# 1-Schematic_EE463_Project.net
KiCad netlist of a schematic drawn in EasyEDA
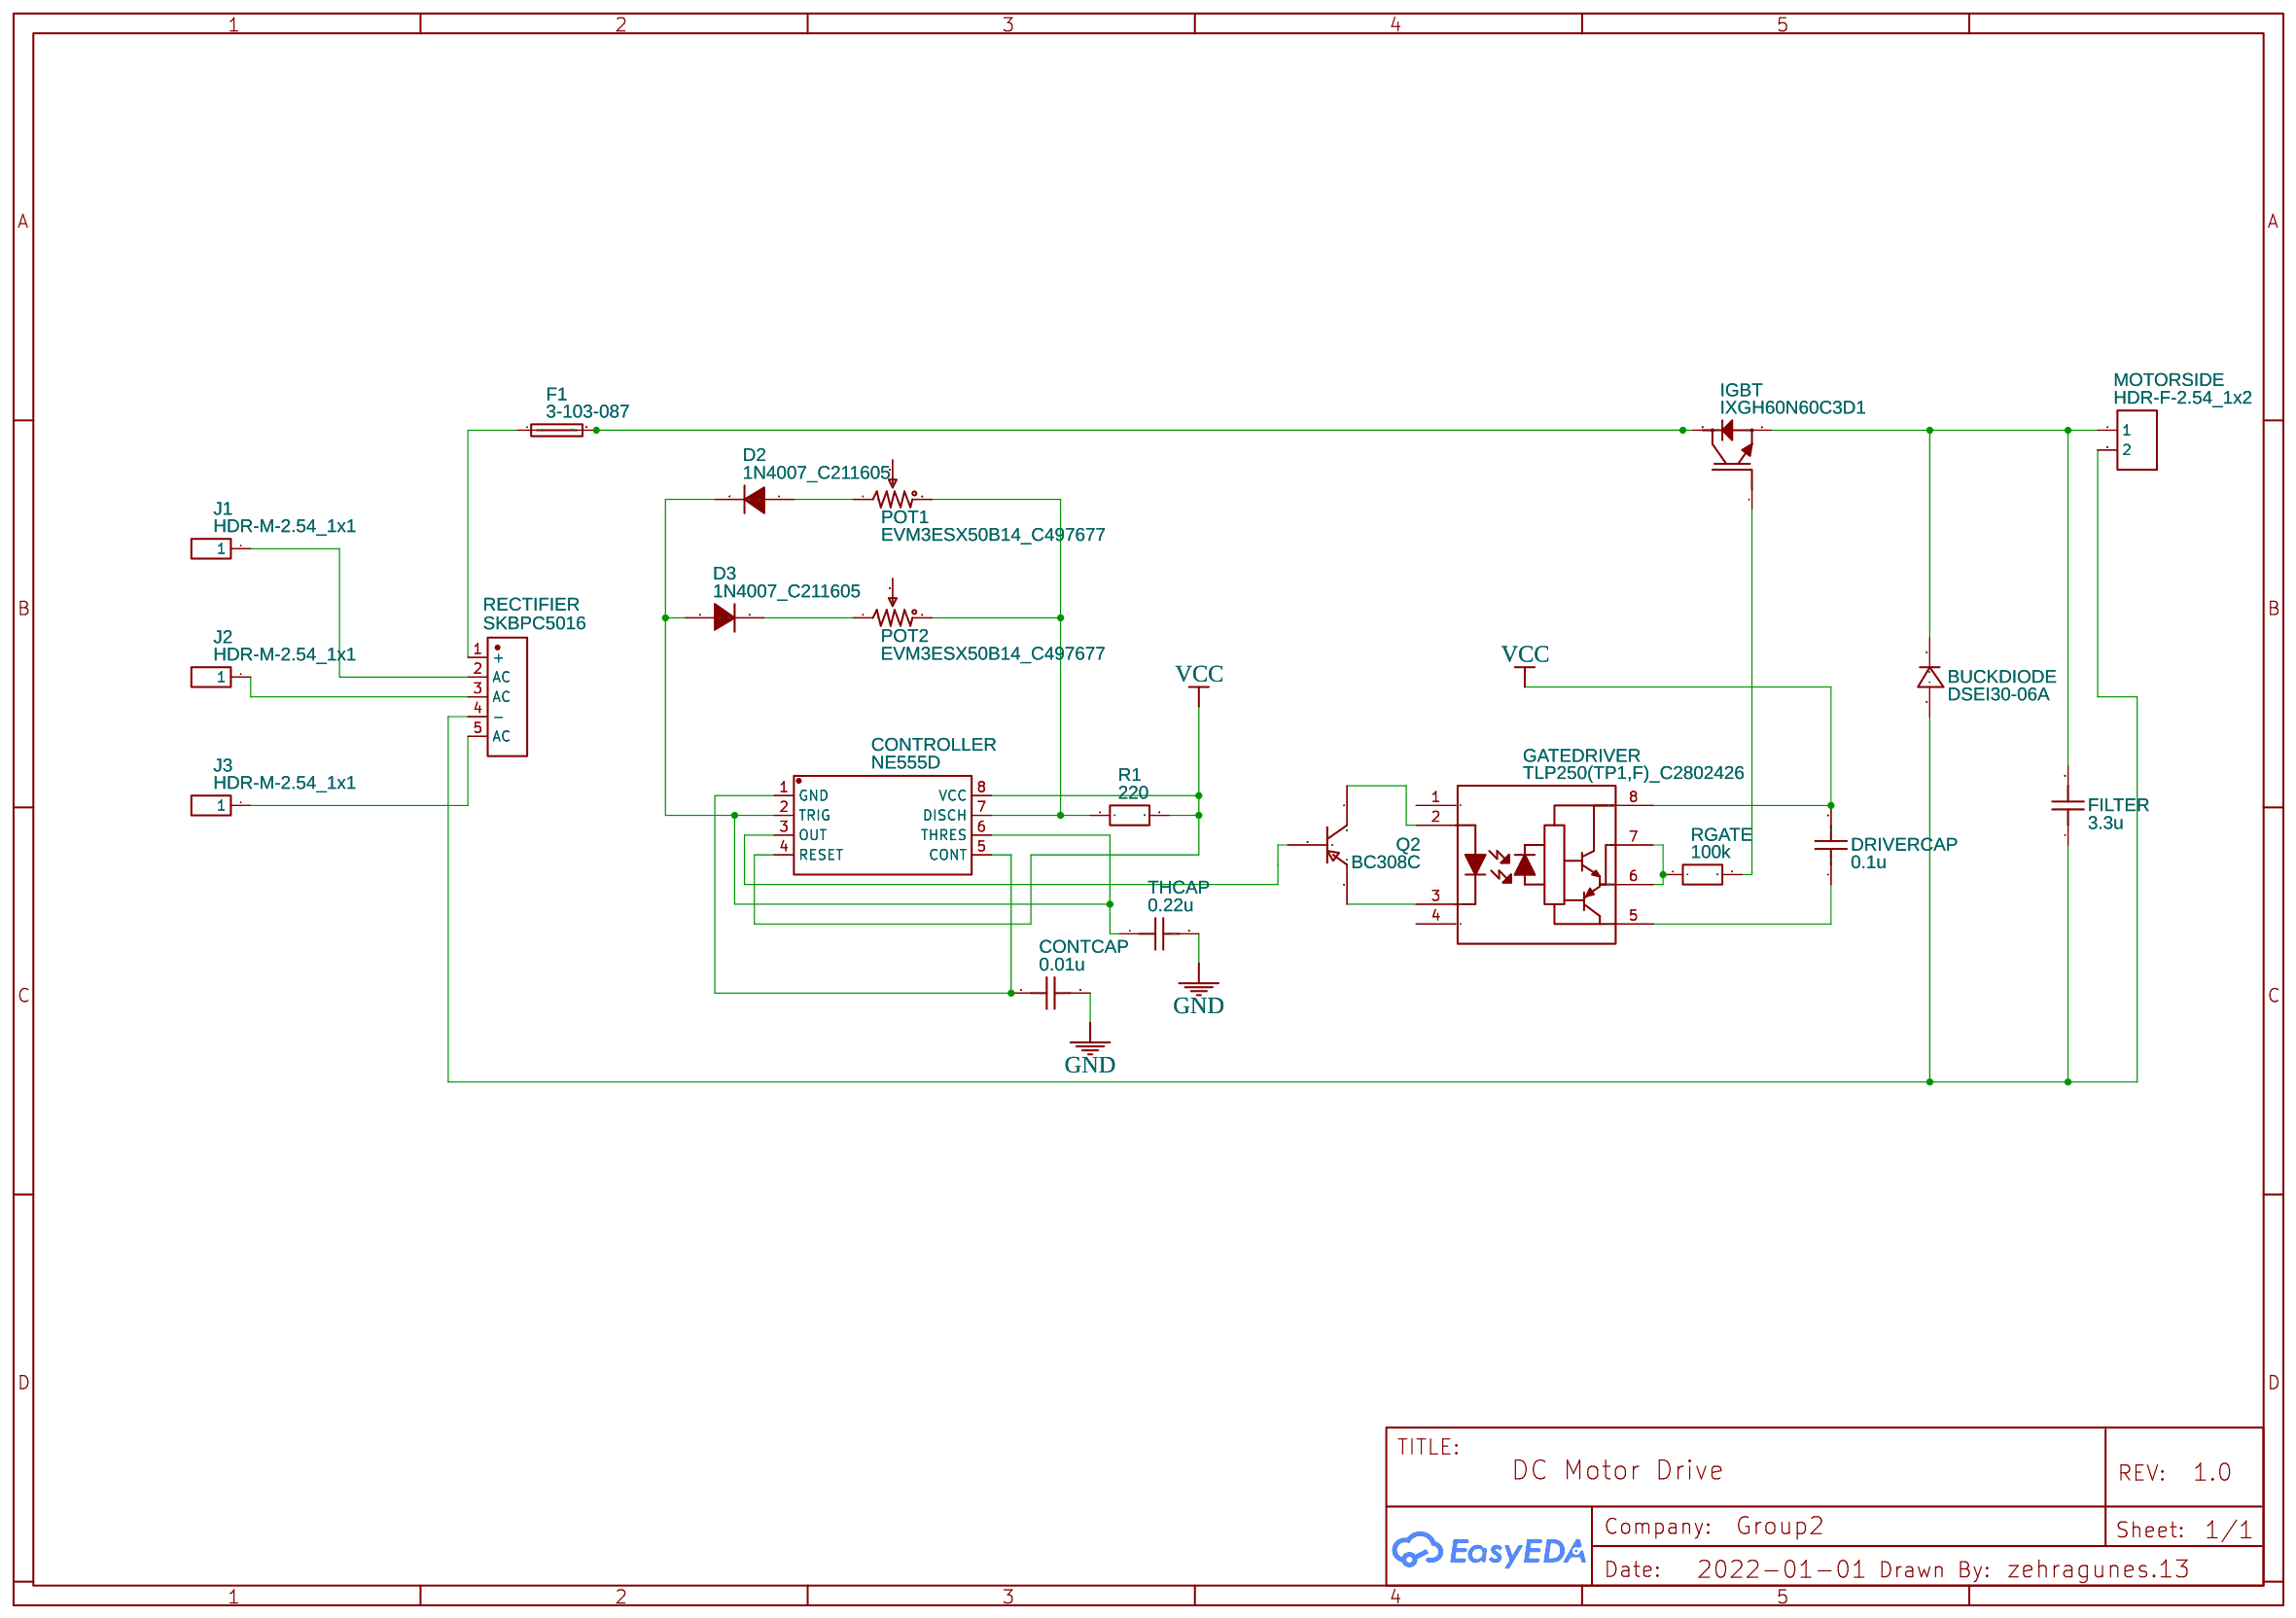
[diagram p0: schematic sheet]

(export (version "E")
  (design (tool "Eeschema 10.0.6"))
  (components
    (comp (ref "BUCKDIODE")
      (value "DSEI30-06A")
      (fields (field (name "BOM_Supplier Part") "C424091"))
      (libsource (lib "") (part "DSEI30-06A"))
    )
    (comp (ref "CONTCAP") (value "0.01u") (libsource (lib "") (part "C_0603_US_2")))
    (comp (ref "CONTROLLER")
      (value "NE555D")
      (fields (field (name "BOM_Supplier Part") "C234230"))
      (libsource (lib "") (part "NE555D"))
    )
    (comp (ref "D2")
      (value "1N4007_C211605")
      (fields (field (name "BOM_Manufacturer Part") "1N4007") (field (name "BOM_Supplier Part") "C211605"))
      (libsource (lib "") (part "1N4007_C211605"))
    )
    (comp (ref "D3")
      (value "1N4007_C211605")
      (fields (field (name "BOM_Manufacturer Part") "1N4007") (field (name "BOM_Supplier Part") "C211605"))
      (libsource (lib "") (part "1N4007_C211605_1"))
    )
    (comp (ref "DRIVERCAP") (value "0.1u") (libsource (lib "") (part "C_0603_US_3")))
    (comp (ref "F1")
      (value "3-103-087")
      (fields (field (name "BOM_Supplier Part") "C1972628"))
      (libsource (lib "") (part "3-103-087"))
    )
    (comp (ref "FILTER") (value "3.3u") (libsource (lib "") (part "C_0603_US_1")))
    (comp (ref "GATEDRIVER")
      (value "TLP250(TP1,F)_C2802426")
      (fields
        (field (name "BOM_Manufacturer Part") "TLP250(TP1,F)")
        (field (name "BOM_Supplier Part") "C2802426")
      )
      (libsource (lib "") (part "TLP250(TP1,F)_C2802426"))
    )
    (comp (ref "IGBT")
      (value "IXGH60N60C3D1")
      (fields (field (name "BOM_Supplier Part") "C497181"))
      (libsource (lib "") (part "IXGH60N60C3D1"))
    )
    (comp (ref "J1")
      (value "HDR-M-2.54_1x1")
      (fields (field (name "BOM_Supplier Part") "C81276"))
      (libsource (lib "") (part "HDR-M-2.54_1x1"))
    )
    (comp (ref "J2")
      (value "HDR-M-2.54_1x1")
      (fields (field (name "BOM_Supplier Part") "C81276"))
      (libsource (lib "") (part "HDR-M-2.54_1x1"))
    )
    (comp (ref "J3")
      (value "HDR-M-2.54_1x1")
      (fields (field (name "BOM_Supplier Part") "C81276"))
      (libsource (lib "") (part "HDR-M-2.54_1x1"))
    )
    (comp (ref "MOTORSIDE")
      (value "HDR-F-2.54_1x2")
      (fields (field (name "BOM_Supplier Part") "C49661"))
      (libsource (lib "") (part "HDR-F-2.54_1x2"))
    )
    (comp (ref "POT1")
      (value "EVM3ESX50B14_C497677")
      (fields
        (field (name "BOM_Manufacturer Part") "EVM3ESX50B14")
        (field (name "BOM_Supplier Part") "C497677")
      )
      (libsource (lib "") (part "EVM3ESX50B14_C497677"))
    )
    (comp (ref "POT2")
      (value "EVM3ESX50B14_C497677")
      (fields
        (field (name "BOM_Manufacturer Part") "EVM3ESX50B14")
        (field (name "BOM_Supplier Part") "C497677")
      )
      (libsource (lib "") (part "EVM3ESX50B14_C497677"))
    )
    (comp (ref "Q2") (value "BC308C") (libsource (lib "") (part "BC308C")))
    (comp (ref "R1") (value "220") (libsource (lib "") (part "R_0201_EU_1")))
    (comp (ref "RECTIFIER")
      (value "SKBPC5016")
      (fields (field (name "BOM_Supplier Part") "C781432"))
      (libsource (lib "") (part "SKBPC5016"))
    )
    (comp (ref "RGATE") (value "100k") (libsource (lib "") (part "R_0201_EU")))
    (comp (ref "THCAP") (value "0.22u") (libsource (lib "") (part "C_0603_US")))
  )
  (nets
    (net (code "1") (name "GND") (class "Default")
      (node (ref "CONTCAP") (pin "2") (pinfunction "2_2") (pintype "unspecified"))
      (node (ref "THCAP") (pin "2") (pinfunction "2_2") (pintype "unspecified"))
    )
    (net (code "2") (name "Net-(BUCKDIODE-A)") (class "Default")
      (node (ref "BUCKDIODE") (pin "3") (pinfunction "A_3") (pintype "unspecified"))
      (node (ref "FILTER") (pin "1") (pinfunction "1_1") (pintype "unspecified"))
      (node (ref "MOTORSIDE") (pin "2") (pinfunction "2_2") (pintype "input"))
      (node (ref "RECTIFIER") (pin "4") (pinfunction "-_4") (pintype "unspecified"))
    )
    (net (code "3") (name "Net-(BUCKDIODE-C)") (class "Default")
      (node (ref "BUCKDIODE") (pin "1") (pinfunction "C_1") (pintype "unspecified"))
      (node (ref "FILTER") (pin "2") (pinfunction "2_2") (pintype "unspecified"))
      (node (ref "IGBT") (pin "3") (pinfunction "E_3") (pintype "input"))
      (node (ref "MOTORSIDE") (pin "1") (pinfunction "1_1") (pintype "input"))
    )
    (net (code "4") (name "Net-(CONTROLLER-CONT)") (class "Default")
      (node (ref "CONTCAP") (pin "1") (pinfunction "1_1") (pintype "unspecified"))
      (node (ref "CONTROLLER") (pin "1") (pinfunction "GND_1") (pintype "unspecified"))
      (node (ref "CONTROLLER") (pin "5") (pinfunction "CONT_5") (pintype "unspecified"))
    )
    (net (code "5") (name "Net-(CONTROLLER-DISCH)") (class "Default")
      (node (ref "CONTROLLER") (pin "7") (pinfunction "DISCH_7") (pintype "unspecified"))
      (node (ref "POT1") (pin "3") (pinfunction "3_3") (pintype "unspecified"))
      (node (ref "POT2") (pin "3") (pinfunction "3_3") (pintype "unspecified"))
      (node (ref "R1") (pin "1") (pinfunction "1_1") (pintype "unspecified"))
    )
    (net (code "6") (name "Net-(CONTROLLER-OUT)") (class "Default")
      (node (ref "CONTROLLER") (pin "3") (pinfunction "OUT_3") (pintype "unspecified"))
      (node (ref "Q2") (pin "2") (pinfunction "B_2") (pintype "unspecified"))
    )
    (net (code "7") (name "Net-(CONTROLLER-THRES)") (class "Default")
      (node (ref "CONTROLLER") (pin "2") (pinfunction "TRIG_2") (pintype "unspecified"))
      (node (ref "CONTROLLER") (pin "6") (pinfunction "THRES_6") (pintype "unspecified"))
      (node (ref "D2") (pin "2") (pinfunction "C_2") (pintype "unspecified"))
      (node (ref "D3") (pin "1") (pinfunction "A_1") (pintype "unspecified"))
      (node (ref "THCAP") (pin "1") (pinfunction "1_1") (pintype "unspecified"))
    )
    (net (code "8") (name "Net-(D2-A)") (class "Default")
      (node (ref "D2") (pin "1") (pinfunction "A_1") (pintype "unspecified"))
      (node (ref "POT1") (pin "1") (pinfunction "1_1") (pintype "unspecified"))
    )
    (net (code "9") (name "Net-(D3-C)") (class "Default")
      (node (ref "D3") (pin "2") (pinfunction "C_2") (pintype "unspecified"))
      (node (ref "POT2") (pin "1") (pinfunction "1_1") (pintype "unspecified"))
    )
    (net (code "10") (name "Net-(GATEDRIVER-GND)") (class "Default")
      (node (ref "DRIVERCAP") (pin "1") (pinfunction "1_1") (pintype "unspecified"))
      (node (ref "GATEDRIVER") (pin "5") (pinfunction "GND_5") (pintype "passive"))
    )
    (net (code "11") (name "Net-(GATEDRIVER-Pad6)") (class "Default")
      (node (ref "GATEDRIVER") (pin "6") (pinfunction "6_6") (pintype "unspecified"))
      (node (ref "GATEDRIVER") (pin "7") (pinfunction "7_7") (pintype "unspecified"))
      (node (ref "RGATE") (pin "1") (pinfunction "1_1") (pintype "unspecified"))
    )
    (net (code "12") (name "Net-(IGBT-C)") (class "Default")
      (node (ref "F1") (pin "2") (pinfunction "2_2") (pintype "unspecified"))
      (node (ref "IGBT") (pin "2") (pinfunction "C_2") (pintype "input"))
    )
    (net (code "13") (name "Net-(IGBT-G)") (class "Default")
      (node (ref "IGBT") (pin "1") (pinfunction "G_1") (pintype "input"))
      (node (ref "RGATE") (pin "2") (pinfunction "2_2") (pintype "unspecified"))
    )
    (net (code "14") (name "Net-(J1-Pad1)") (class "Default")
      (node (ref "J1") (pin "1") (pinfunction "1_1") (pintype "input"))
      (node (ref "RECTIFIER") (pin "2") (pinfunction "AC_2") (pintype "unspecified"))
    )
    (net (code "15") (name "Net-(J2-Pad1)") (class "Default")
      (node (ref "J2") (pin "1") (pinfunction "1_1") (pintype "input"))
      (node (ref "RECTIFIER") (pin "3") (pinfunction "AC_3") (pintype "unspecified"))
    )
    (net (code "16") (name "Net-(J3-Pad1)") (class "Default")
      (node (ref "J3") (pin "1") (pinfunction "1_1") (pintype "input"))
      (node (ref "RECTIFIER") (pin "5") (pinfunction "AC_5") (pintype "unspecified"))
    )
    (net (code "17") (name "Net-(Q2-C)") (class "Default")
      (node (ref "GATEDRIVER") (pin "2") (pinfunction "2_2") (pintype "unspecified"))
      (node (ref "Q2") (pin "1") (pinfunction "C_1") (pintype "unspecified"))
    )
    (net (code "18") (name "Net-(Q2-E)") (class "Default")
      (node (ref "GATEDRIVER") (pin "3") (pinfunction "3_3") (pintype "unspecified"))
      (node (ref "Q2") (pin "3") (pinfunction "E_3") (pintype "unspecified"))
    )
    (net (code "19") (name "Net-(RECTIFIER-+)") (class "Default")
      (node (ref "F1") (pin "1") (pinfunction "1_1") (pintype "unspecified"))
      (node (ref "RECTIFIER") (pin "1") (pinfunction "+_1") (pintype "unspecified"))
    )
    (net (code "20") (name "VCC") (class "Default")
      (node (ref "CONTROLLER") (pin "4") (pinfunction "RESET_4") (pintype "unspecified"))
      (node (ref "CONTROLLER") (pin "8") (pinfunction "VCC_8") (pintype "unspecified"))
      (node (ref "DRIVERCAP") (pin "2") (pinfunction "2_2") (pintype "unspecified"))
      (node (ref "GATEDRIVER") (pin "8") (pinfunction "VCC_8") (pintype "passive"))
      (node (ref "R1") (pin "2") (pinfunction "2_2") (pintype "unspecified"))
    )
    (net (code "21") (name "unconnected-(GATEDRIVER-Pad1)") (class "Default")
      (node (ref "GATEDRIVER") (pin "1") (pinfunction "1_1") (pintype "unspecified"))
    )
    (net (code "22") (name "unconnected-(GATEDRIVER-Pad4)") (class "Default")
      (node (ref "GATEDRIVER") (pin "4") (pinfunction "4_4") (pintype "unspecified"))
    )
    (net (code "23") (name "unconnected-(POT1-Pad2)") (class "Default")
      (node (ref "POT1") (pin "2") (pinfunction "2_2") (pintype "unspecified"))
    )
    (net (code "24") (name "unconnected-(POT2-Pad2)") (class "Default")
      (node (ref "POT2") (pin "2") (pinfunction "2_2") (pintype "unspecified"))
    )
  )
)
